# 04_ADD.net
KiCad netlist of a schematic drawn in EAGLE
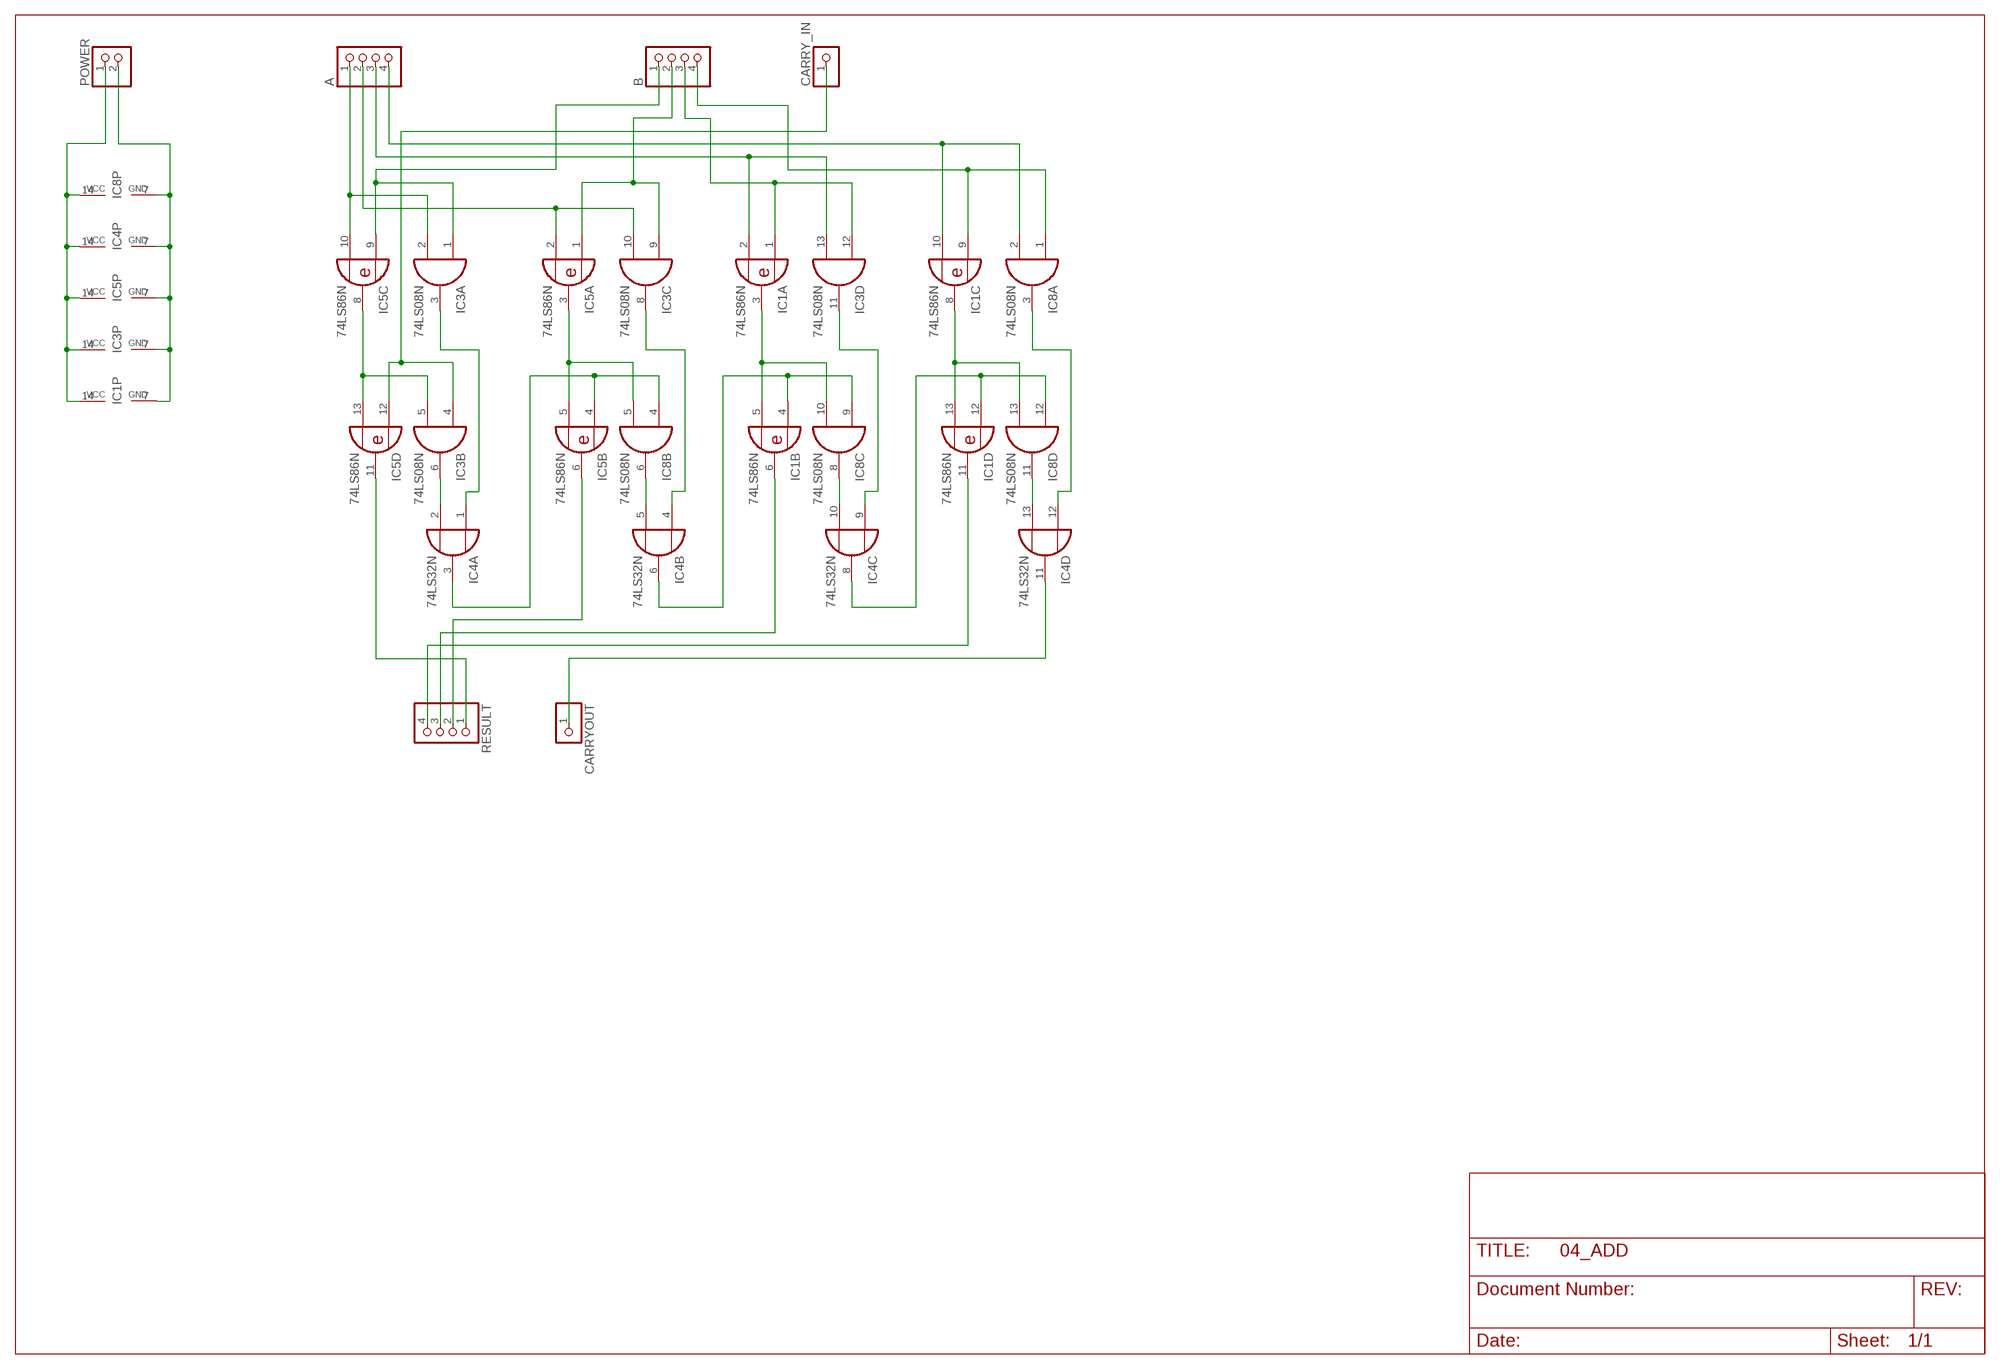
[diagram p0: schematic, sheet 1]

(export (version "E")
  (design (tool "Eeschema 10.0.6"))
  (components
    (comp (ref "A")
      (value "PINHD-1X4")
      (footprint "eagle-import:1X04")
      (libsource (lib "eagle-import") (part "PINHD-1X4"))
    )
    (comp (ref "B")
      (value "PINHD-1X4")
      (footprint "eagle-import:1X04")
      (libsource (lib "eagle-import") (part "PINHD-1X4"))
    )
    (comp (ref "CARRYOUT")
      (value "PINHD-1X1")
      (footprint "eagle-import:1X01")
      (libsource (lib "eagle-import") (part "PINHD-1X1"))
    )
    (comp (ref "CARRY_IN")
      (value "PINHD-1X1")
      (footprint "eagle-import:1X01")
      (libsource (lib "eagle-import") (part "PINHD-1X1"))
    )
    (comp (ref "IC1")
      (value "74LS86N")
      (footprint "eagle-import:DIL14")
      (libsource (lib "eagle-import") (part "7486NLS"))
    )
    (comp (ref "IC3")
      (value "74LS08N")
      (footprint "eagle-import:DIL14")
      (libsource (lib "eagle-import") (part "7408NLS"))
    )
    (comp (ref "IC4")
      (value "74LS32N")
      (footprint "eagle-import:DIL14")
      (libsource (lib "eagle-import") (part "7432NLS"))
    )
    (comp (ref "IC5")
      (value "74LS86N")
      (footprint "eagle-import:DIL14")
      (libsource (lib "eagle-import") (part "7486NLS"))
    )
    (comp (ref "IC8")
      (value "74LS08N")
      (footprint "eagle-import:DIL14")
      (libsource (lib "eagle-import") (part "7408NLS"))
    )
    (comp (ref "POWER")
      (value "PINHD-1X2")
      (footprint "eagle-import:1X02")
      (libsource (lib "eagle-import") (part "PINHD-1X2"))
    )
    (comp (ref "RESULT")
      (value "PINHD-1X4")
      (footprint "eagle-import:1X04")
      (libsource (lib "eagle-import") (part "PINHD-1X4"))
    )
  )
  (nets
    (net (code "1") (name "Net-(IC1A-I0)") (class "Default")
      (node (ref "B") (pin "3") (pinfunction "3_3") (pintype "passive"))
      (node (ref "IC1") (pin "1") (pinfunction "I0_1") (pintype "input"))
      (node (ref "IC3") (pin "12") (pinfunction "I0_12") (pintype "input"))
    )
    (net (code "2") (name "Net-(IC1A-I1)") (class "Default")
      (node (ref "A") (pin "3") (pinfunction "3_3") (pintype "passive"))
      (node (ref "IC1") (pin "2") (pinfunction "I1_2") (pintype "input"))
      (node (ref "IC3") (pin "13") (pinfunction "I1_13") (pintype "input"))
    )
    (net (code "3") (name "Net-(IC1A-O)") (class "Default")
      (node (ref "IC1") (pin "3") (pinfunction "O_3") (pintype "output"))
      (node (ref "IC1") (pin "5") (pinfunction "I1_5") (pintype "input"))
      (node (ref "IC8") (pin "10") (pinfunction "I1_10") (pintype "input"))
    )
    (net (code "4") (name "Net-(IC1B-I0)") (class "Default")
      (node (ref "IC1") (pin "4") (pinfunction "I0_4") (pintype "input"))
      (node (ref "IC4") (pin "6") (pinfunction "O_6") (pintype "output"))
      (node (ref "IC8") (pin "9") (pinfunction "I0_9") (pintype "input"))
    )
    (net (code "5") (name "Net-(IC1B-O)") (class "Default")
      (node (ref "IC1") (pin "6") (pinfunction "O_6") (pintype "output"))
      (node (ref "RESULT") (pin "3") (pinfunction "3_3") (pintype "passive"))
    )
    (net (code "6") (name "Net-(IC1C-I0)") (class "Default")
      (node (ref "B") (pin "4") (pinfunction "4_4") (pintype "passive"))
      (node (ref "IC1") (pin "9") (pinfunction "I0_9") (pintype "input"))
      (node (ref "IC8") (pin "1") (pinfunction "I0_1") (pintype "input"))
    )
    (net (code "7") (name "Net-(IC1C-I1)") (class "Default")
      (node (ref "A") (pin "4") (pinfunction "4_4") (pintype "passive"))
      (node (ref "IC1") (pin "10") (pinfunction "I1_10") (pintype "input"))
      (node (ref "IC8") (pin "2") (pinfunction "I1_2") (pintype "input"))
    )
    (net (code "8") (name "Net-(IC1C-O)") (class "Default")
      (node (ref "IC1") (pin "13") (pinfunction "I1_13") (pintype "input"))
      (node (ref "IC1") (pin "8") (pinfunction "O_8") (pintype "output"))
      (node (ref "IC8") (pin "13") (pinfunction "I1_13") (pintype "input"))
    )
    (net (code "9") (name "Net-(IC1D-I0)") (class "Default")
      (node (ref "IC1") (pin "12") (pinfunction "I0_12") (pintype "input"))
      (node (ref "IC4") (pin "8") (pinfunction "O_8") (pintype "output"))
      (node (ref "IC8") (pin "12") (pinfunction "I0_12") (pintype "input"))
    )
    (net (code "10") (name "Net-(IC1D-O)") (class "Default")
      (node (ref "IC1") (pin "11") (pinfunction "O_11") (pintype "output"))
      (node (ref "RESULT") (pin "4") (pinfunction "4_4") (pintype "passive"))
    )
    (net (code "11") (name "Net-(IC1E-GND)") (class "Default")
      (node (ref "IC1") (pin "7") (pinfunction "GND_7") (pintype "power_in"))
      (node (ref "IC3") (pin "7") (pinfunction "GND_7") (pintype "power_in"))
      (node (ref "IC4") (pin "7") (pinfunction "GND_7") (pintype "power_in"))
      (node (ref "IC5") (pin "7") (pinfunction "GND_7") (pintype "power_in"))
      (node (ref "IC8") (pin "7") (pinfunction "GND_7") (pintype "power_in"))
      (node (ref "POWER") (pin "2") (pinfunction "2_2") (pintype "passive"))
    )
    (net (code "12") (name "Net-(IC1E-VCC)") (class "Default")
      (node (ref "IC1") (pin "14") (pinfunction "VCC_14") (pintype "power_in"))
      (node (ref "IC3") (pin "14") (pinfunction "VCC_14") (pintype "power_in"))
      (node (ref "IC4") (pin "14") (pinfunction "VCC_14") (pintype "power_in"))
      (node (ref "IC5") (pin "14") (pinfunction "VCC_14") (pintype "power_in"))
      (node (ref "IC8") (pin "14") (pinfunction "VCC_14") (pintype "power_in"))
      (node (ref "POWER") (pin "1") (pinfunction "1_1") (pintype "passive"))
    )
    (net (code "13") (name "Net-(IC3A-I0)") (class "Default")
      (node (ref "B") (pin "1") (pinfunction "1_1") (pintype "passive"))
      (node (ref "IC3") (pin "1") (pinfunction "I0_1") (pintype "input"))
      (node (ref "IC5") (pin "9") (pinfunction "I0_9") (pintype "input"))
    )
    (net (code "14") (name "Net-(IC3A-I1)") (class "Default")
      (node (ref "A") (pin "1") (pinfunction "1_1") (pintype "passive"))
      (node (ref "IC3") (pin "2") (pinfunction "I1_2") (pintype "input"))
      (node (ref "IC5") (pin "10") (pinfunction "I1_10") (pintype "input"))
    )
    (net (code "15") (name "Net-(IC3A-O)") (class "Default")
      (node (ref "IC3") (pin "3") (pinfunction "O_3") (pintype "output"))
      (node (ref "IC4") (pin "1") (pinfunction "I0_1") (pintype "input"))
    )
    (net (code "16") (name "Net-(IC3B-I0)") (class "Default")
      (node (ref "CARRY_IN") (pin "1") (pinfunction "1_1") (pintype "passive"))
      (node (ref "IC3") (pin "4") (pinfunction "I0_4") (pintype "input"))
      (node (ref "IC5") (pin "12") (pinfunction "I0_12") (pintype "input"))
    )
    (net (code "17") (name "Net-(IC3B-I1)") (class "Default")
      (node (ref "IC3") (pin "5") (pinfunction "I1_5") (pintype "input"))
      (node (ref "IC5") (pin "13") (pinfunction "I1_13") (pintype "input"))
      (node (ref "IC5") (pin "8") (pinfunction "O_8") (pintype "output"))
    )
    (net (code "18") (name "Net-(IC3B-O)") (class "Default")
      (node (ref "IC3") (pin "6") (pinfunction "O_6") (pintype "output"))
      (node (ref "IC4") (pin "2") (pinfunction "I1_2") (pintype "input"))
    )
    (net (code "19") (name "Net-(IC3C-I0)") (class "Default")
      (node (ref "B") (pin "2") (pinfunction "2_2") (pintype "passive"))
      (node (ref "IC3") (pin "9") (pinfunction "I0_9") (pintype "input"))
      (node (ref "IC5") (pin "1") (pinfunction "I0_1") (pintype "input"))
    )
    (net (code "20") (name "Net-(IC3C-I1)") (class "Default")
      (node (ref "A") (pin "2") (pinfunction "2_2") (pintype "passive"))
      (node (ref "IC3") (pin "10") (pinfunction "I1_10") (pintype "input"))
      (node (ref "IC5") (pin "2") (pinfunction "I1_2") (pintype "input"))
    )
    (net (code "21") (name "Net-(IC3C-O)") (class "Default")
      (node (ref "IC3") (pin "8") (pinfunction "O_8") (pintype "output"))
      (node (ref "IC4") (pin "4") (pinfunction "I0_4") (pintype "input"))
    )
    (net (code "22") (name "Net-(IC3D-O)") (class "Default")
      (node (ref "IC3") (pin "11") (pinfunction "O_11") (pintype "output"))
      (node (ref "IC4") (pin "9") (pinfunction "I0_9") (pintype "input"))
    )
    (net (code "23") (name "Net-(IC4A-O)") (class "Default")
      (node (ref "IC4") (pin "3") (pinfunction "O_3") (pintype "output"))
      (node (ref "IC5") (pin "4") (pinfunction "I0_4") (pintype "input"))
      (node (ref "IC8") (pin "4") (pinfunction "I0_4") (pintype "input"))
    )
    (net (code "24") (name "Net-(IC4B-I1)") (class "Default")
      (node (ref "IC4") (pin "5") (pinfunction "I1_5") (pintype "input"))
      (node (ref "IC8") (pin "6") (pinfunction "O_6") (pintype "output"))
    )
    (net (code "25") (name "Net-(IC4C-I1)") (class "Default")
      (node (ref "IC4") (pin "10") (pinfunction "I1_10") (pintype "input"))
      (node (ref "IC8") (pin "8") (pinfunction "O_8") (pintype "output"))
    )
    (net (code "26") (name "Net-(IC4D-I0)") (class "Default")
      (node (ref "IC4") (pin "12") (pinfunction "I0_12") (pintype "input"))
      (node (ref "IC8") (pin "3") (pinfunction "O_3") (pintype "output"))
    )
    (net (code "27") (name "Net-(IC4D-I1)") (class "Default")
      (node (ref "IC4") (pin "13") (pinfunction "I1_13") (pintype "input"))
      (node (ref "IC8") (pin "11") (pinfunction "O_11") (pintype "output"))
    )
    (net (code "28") (name "Net-(IC4D-O)") (class "Default")
      (node (ref "CARRYOUT") (pin "1") (pinfunction "1_1") (pintype "passive"))
      (node (ref "IC4") (pin "11") (pinfunction "O_11") (pintype "output"))
    )
    (net (code "29") (name "Net-(IC5A-O)") (class "Default")
      (node (ref "IC5") (pin "3") (pinfunction "O_3") (pintype "output"))
      (node (ref "IC5") (pin "5") (pinfunction "I1_5") (pintype "input"))
      (node (ref "IC8") (pin "5") (pinfunction "I1_5") (pintype "input"))
    )
    (net (code "30") (name "Net-(IC5B-O)") (class "Default")
      (node (ref "IC5") (pin "6") (pinfunction "O_6") (pintype "output"))
      (node (ref "RESULT") (pin "2") (pinfunction "2_2") (pintype "passive"))
    )
    (net (code "31") (name "Net-(IC5D-O)") (class "Default")
      (node (ref "IC5") (pin "11") (pinfunction "O_11") (pintype "output"))
      (node (ref "RESULT") (pin "1") (pinfunction "1_1") (pintype "passive"))
    )
  )
)
